# untitled.net
KiCad netlist of a schematic drawn in EAGLE
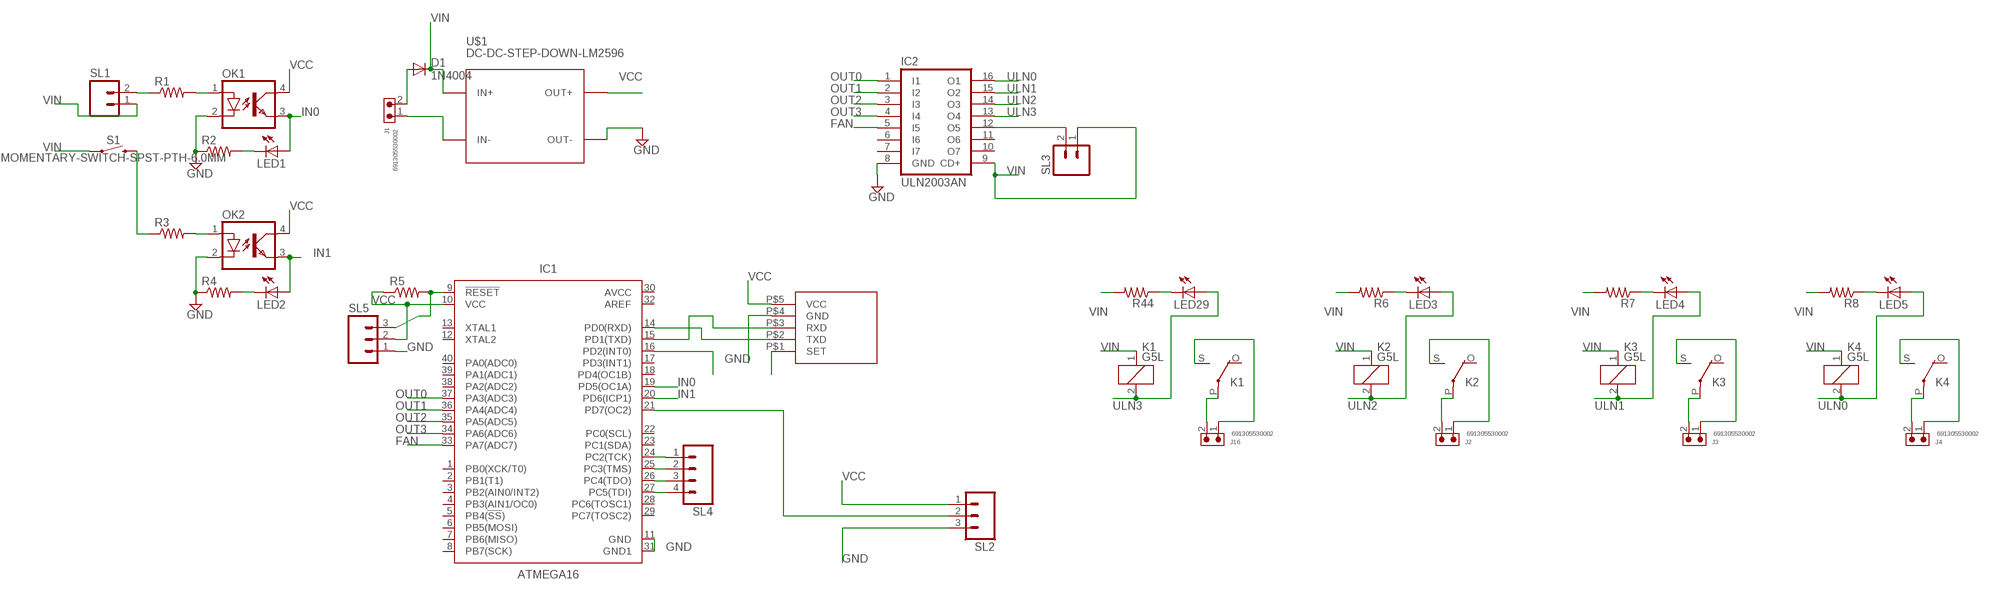
[diagram p0: schematic, sheet 1]

(export (version "E")
  (design (tool "Eeschema 10.0.6"))
  (components
    (comp (ref "D1")
      (value "1N4004")
      (footprint "eagle-import:DO41-10")
      (libsource (lib "eagle-import") (part "1N4004"))
    )
    (comp (ref "IC1")
      (value "ATMEGA16")
      (footprint "eagle-import:DIP1587W56P254L5229H482Q40B")
      (fields (field (name "MANUFACTURER") "Microchip Technology") (field (name "MPN") "ATMEGA32-16PU"))
      (libsource (lib "eagle-import") (part "ATMEGA32DIP-16PU_"))
    )
    (comp (ref "IC2")
      (value "ULN2003AN")
      (footprint "eagle-import:DIL16")
      (libsource (lib "eagle-import") (part "ULN2003AN"))
    )
    (comp (ref "J1")
      (value "691305530002")
      (footprint "eagle-import:691305530002")
      (libsource (lib "eagle-import") (part "691305530002"))
    )
    (comp (ref "J2")
      (value "691305530002")
      (footprint "eagle-import:691305530002")
      (libsource (lib "eagle-import") (part "691305530002"))
    )
    (comp (ref "J3")
      (value "691305530002")
      (footprint "eagle-import:691305530002")
      (libsource (lib "eagle-import") (part "691305530002"))
    )
    (comp (ref "J4")
      (value "691305530002")
      (footprint "eagle-import:691305530002")
      (libsource (lib "eagle-import") (part "691305530002"))
    )
    (comp (ref "J16")
      (value "691305530002")
      (footprint "eagle-import:691305530002")
      (libsource (lib "eagle-import") (part "691305530002"))
    )
    (comp (ref "K1")
      (value "G5L")
      (footprint "eagle-import:G5LE")
      (libsource (lib "eagle-import") (part "G5L"))
    )
    (comp (ref "K2")
      (value "G5L")
      (footprint "eagle-import:G5LE")
      (libsource (lib "eagle-import") (part "G5L"))
    )
    (comp (ref "K3")
      (value "G5L")
      (footprint "eagle-import:G5LE")
      (libsource (lib "eagle-import") (part "G5L"))
    )
    (comp (ref "K4")
      (value "G5L")
      (footprint "eagle-import:G5LE")
      (libsource (lib "eagle-import") (part "G5L"))
    )
    (comp (ref "LED1")
      (value "LED5MM")
      (footprint "eagle-import:LED5MM")
      (libsource (lib "eagle-import") (part "LED5MM"))
    )
    (comp (ref "LED2")
      (value "LED5MM")
      (footprint "eagle-import:LED5MM")
      (libsource (lib "eagle-import") (part "LED5MM"))
    )
    (comp (ref "LED3")
      (value "LED5MM")
      (footprint "eagle-import:LED5MM")
      (libsource (lib "eagle-import") (part "LED5MM"))
    )
    (comp (ref "LED4")
      (value "LED5MM")
      (footprint "eagle-import:LED5MM")
      (libsource (lib "eagle-import") (part "LED5MM"))
    )
    (comp (ref "LED5")
      (value "LED5MM")
      (footprint "eagle-import:LED5MM")
      (libsource (lib "eagle-import") (part "LED5MM"))
    )
    (comp (ref "LED29")
      (value "LED5MM")
      (footprint "eagle-import:LED5MM")
      (libsource (lib "eagle-import") (part "LED5MM"))
    )
    (comp (ref "OK1")
      (value "PC817")
      (footprint "eagle-import:DIL04")
      (fields (field (name "MPN") "PC817X4J000F"))
      (libsource (lib "eagle-import") (part "PC817"))
    )
    (comp (ref "OK2")
      (value "PC817")
      (footprint "eagle-import:DIL04")
      (fields (field (name "MPN") "PC817X4J000F"))
      (libsource (lib "eagle-import") (part "PC817"))
    )
    (comp (ref "R1")
      (value "R-US_0207/7")
      (footprint "eagle-import:0207_7")
      (libsource (lib "eagle-import") (part "R-US_0207/7"))
    )
    (comp (ref "R2")
      (value "R-US_0207/7")
      (footprint "eagle-import:0207_7")
      (libsource (lib "eagle-import") (part "R-US_0207/7"))
    )
    (comp (ref "R3")
      (value "R-US_0207/7")
      (footprint "eagle-import:0207_7")
      (libsource (lib "eagle-import") (part "R-US_0207/7"))
    )
    (comp (ref "R4")
      (value "R-US_0207/7")
      (footprint "eagle-import:0207_7")
      (libsource (lib "eagle-import") (part "R-US_0207/7"))
    )
    (comp (ref "R5")
      (value "R-US_0207/7")
      (footprint "eagle-import:0207_7")
      (libsource (lib "eagle-import") (part "R-US_0207/7"))
    )
    (comp (ref "R6")
      (value "R-US_0207/7")
      (footprint "eagle-import:0207_7")
      (libsource (lib "eagle-import") (part "R-US_0207/7"))
    )
    (comp (ref "R7")
      (value "R-US_0207/7")
      (footprint "eagle-import:0207_7")
      (libsource (lib "eagle-import") (part "R-US_0207/7"))
    )
    (comp (ref "R8")
      (value "R-US_0207/7")
      (footprint "eagle-import:0207_7")
      (libsource (lib "eagle-import") (part "R-US_0207/7"))
    )
    (comp (ref "R44")
      (value "R-US_0207/7")
      (footprint "eagle-import:0207_7")
      (libsource (lib "eagle-import") (part "R-US_0207/7"))
    )
    (comp (ref "S1")
      (value "MOMENTARY-SWITCH-SPST-PTH-6.0MM")
      (footprint "eagle-import:TACTILE_SWITCH_PTH_6.0MM")
      (libsource (lib "eagle-import") (part "MOMENTARY-SWITCH-SPST-PTH-6.0MM"))
    )
    (comp (ref "SL1")
      (value "M02")
      (footprint "eagle-import:02P")
      (libsource (lib "eagle-import") (part "M02"))
    )
    (comp (ref "SL2")
      (value "M03")
      (footprint "eagle-import:03P")
      (libsource (lib "eagle-import") (part "M03"))
    )
    (comp (ref "SL3")
      (value "M02")
      (footprint "eagle-import:02P")
      (libsource (lib "eagle-import") (part "M02"))
    )
    (comp (ref "SL4")
      (value "M04")
      (footprint "eagle-import:04P")
      (libsource (lib "eagle-import") (part "M04"))
    )
    (comp (ref "SL5")
      (value "M03")
      (footprint "eagle-import:03P")
      (libsource (lib "eagle-import") (part "M03"))
    )
    (comp (ref "U$1")
      (value "DC-DC-STEP-DOWN-LM2596")
      (footprint "eagle-import:DC-DC-STEP-DOWN-LM2596")
      (libsource (lib "eagle-import") (part "DC-DC-STEP-DOWN-LM2596"))
    )
    (comp (ref "U$2")
      (value "HC12")
      (footprint "eagle-import:HC12")
      (libsource (lib "eagle-import") (part "HC12"))
    )
  )
  (nets
    (net (code "1") (name "/AVCC") (class "Default")
      (node (ref "IC1") (pin "30") (pinfunction "AVCC_30") (pintype "power_in"))
    )
    (net (code "2") (name "/FAN") (class "Default")
      (node (ref "IC1") (pin "33") (pinfunction "PA7(ADC7)_33") (pintype "bidirectional"))
      (node (ref "IC2") (pin "5") (pinfunction "I5_5") (pintype "input"))
    )
    (net (code "3") (name "/IN0") (class "Default")
      (node (ref "IC1") (pin "19") (pinfunction "PD5(OC1A)_19") (pintype "bidirectional"))
      (node (ref "LED1") (pin "A") (pinfunction "A_A") (pintype "passive"))
      (node (ref "OK1") (pin "3") (pinfunction "EMIT_3") (pintype "passive"))
    )
    (net (code "4") (name "/IN1") (class "Default")
      (node (ref "IC1") (pin "20") (pinfunction "PD6(ICP1)_20") (pintype "bidirectional"))
      (node (ref "LED2") (pin "A") (pinfunction "A_A") (pintype "passive"))
      (node (ref "OK2") (pin "3") (pinfunction "EMIT_3") (pintype "passive"))
    )
    (net (code "5") (name "/OUT0") (class "Default")
      (node (ref "IC1") (pin "37") (pinfunction "PA3(ADC3)_37") (pintype "bidirectional"))
      (node (ref "IC2") (pin "1") (pinfunction "I1_1") (pintype "input"))
    )
    (net (code "6") (name "/OUT1") (class "Default")
      (node (ref "IC1") (pin "36") (pinfunction "PA4(ADC4)_36") (pintype "bidirectional"))
      (node (ref "IC2") (pin "2") (pinfunction "I2_2") (pintype "input"))
    )
    (net (code "7") (name "/OUT2") (class "Default")
      (node (ref "IC1") (pin "35") (pinfunction "PA5(ADC5)_35") (pintype "bidirectional"))
      (node (ref "IC2") (pin "3") (pinfunction "I3_3") (pintype "input"))
    )
    (net (code "8") (name "/OUT3") (class "Default")
      (node (ref "IC1") (pin "34") (pinfunction "PA6(ADC6)_34") (pintype "bidirectional"))
      (node (ref "IC2") (pin "4") (pinfunction "I4_4") (pintype "input"))
    )
    (net (code "9") (name "/ULN0") (class "Default")
      (node (ref "IC2") (pin "16") (pinfunction "O1_16") (pintype "open_collector"))
      (node (ref "K4") (pin "2") (pinfunction "2_2") (pintype "passive"))
      (node (ref "LED5") (pin "A") (pinfunction "A_A") (pintype "passive"))
    )
    (net (code "10") (name "/ULN1") (class "Default")
      (node (ref "IC2") (pin "15") (pinfunction "O2_15") (pintype "open_collector"))
      (node (ref "K3") (pin "2") (pinfunction "2_2") (pintype "passive"))
      (node (ref "LED4") (pin "A") (pinfunction "A_A") (pintype "passive"))
    )
    (net (code "11") (name "/ULN2") (class "Default")
      (node (ref "IC2") (pin "14") (pinfunction "O3_14") (pintype "open_collector"))
      (node (ref "K2") (pin "2") (pinfunction "2_2") (pintype "passive"))
      (node (ref "LED3") (pin "A") (pinfunction "A_A") (pintype "passive"))
    )
    (net (code "12") (name "/ULN3") (class "Default")
      (node (ref "IC2") (pin "13") (pinfunction "O4_13") (pintype "open_collector"))
      (node (ref "K1") (pin "2") (pinfunction "2_2") (pintype "passive"))
      (node (ref "LED29") (pin "A") (pinfunction "A_A") (pintype "passive"))
    )
    (net (code "13") (name "/VCC") (class "Default")
      (node (ref "IC1") (pin "10") (pinfunction "VCC_10") (pintype "power_in"))
      (node (ref "OK1") (pin "4") (pinfunction "COL_4") (pintype "passive"))
      (node (ref "OK2") (pin "4") (pinfunction "COL_4") (pintype "passive"))
      (node (ref "R5") (pin "1") (pinfunction "1_1") (pintype "passive"))
      (node (ref "SL2") (pin "1") (pinfunction "1_1") (pintype "passive"))
      (node (ref "SL5") (pin "2") (pinfunction "2_2") (pintype "passive"))
      (node (ref "U$1") (pin "OUT+") (pinfunction "OUT+_OUT+") (pintype "bidirectional"))
      (node (ref "U$2") (pin "P$5") (pinfunction "VCC_P$5") (pintype "bidirectional"))
    )
    (net (code "14") (name "/VIN") (class "Default")
      (node (ref "D1") (pin "C") (pinfunction "C_C") (pintype "passive"))
      (node (ref "IC2") (pin "9") (pinfunction "CD+_9") (pintype "passive"))
      (node (ref "K1") (pin "1") (pinfunction "1_1") (pintype "passive"))
      (node (ref "K2") (pin "1") (pinfunction "1_1") (pintype "passive"))
      (node (ref "K3") (pin "1") (pinfunction "1_1") (pintype "passive"))
      (node (ref "K4") (pin "1") (pinfunction "1_1") (pintype "passive"))
      (node (ref "R44") (pin "2") (pinfunction "2_2") (pintype "passive"))
      (node (ref "R6") (pin "2") (pinfunction "2_2") (pintype "passive"))
      (node (ref "R7") (pin "2") (pinfunction "2_2") (pintype "passive"))
      (node (ref "R8") (pin "2") (pinfunction "2_2") (pintype "passive"))
      (node (ref "S1") (pin "1") (pinfunction "1_1") (pintype "passive"))
      (node (ref "SL1") (pin "1") (pinfunction "1_1") (pintype "passive"))
      (node (ref "SL3") (pin "1") (pinfunction "1_1") (pintype "passive"))
      (node (ref "U$1") (pin "IN+") (pinfunction "IN+_IN+") (pintype "bidirectional"))
    )
    (net (code "15") (name "GND") (class "Default")
      (node (ref "IC1") (pin "11") (pinfunction "GND_11") (pintype "power_in"))
      (node (ref "IC1") (pin "31") (pinfunction "GND1_31") (pintype "power_in"))
      (node (ref "IC2") (pin "8") (pinfunction "GND_8") (pintype "power_in"))
      (node (ref "OK1") (pin "2") (pinfunction "C_2") (pintype "passive"))
      (node (ref "OK2") (pin "2") (pinfunction "C_2") (pintype "passive"))
      (node (ref "R2") (pin "1") (pinfunction "1_1") (pintype "passive"))
      (node (ref "R4") (pin "1") (pinfunction "1_1") (pintype "passive"))
      (node (ref "SL2") (pin "3") (pinfunction "3_3") (pintype "passive"))
      (node (ref "SL5") (pin "1") (pinfunction "1_1") (pintype "passive"))
      (node (ref "U$1") (pin "OUT-") (pinfunction "OUT-_OUT-") (pintype "bidirectional"))
      (node (ref "U$2") (pin "P$4") (pinfunction "GND_P$4") (pintype "bidirectional"))
    )
    (net (code "16") (name "Net-(D1-PadA)") (class "Default")
      (node (ref "D1") (pin "A") (pinfunction "A_A") (pintype "passive"))
      (node (ref "J1") (pin "2") (pinfunction "2_2") (pintype "passive"))
    )
    (net (code "17") (name "Net-(IC1-PC2(TCK))") (class "Default")
      (node (ref "IC1") (pin "24") (pinfunction "PC2(TCK)_24") (pintype "input"))
      (node (ref "SL4") (pin "1") (pinfunction "1_1") (pintype "passive"))
    )
    (net (code "18") (name "Net-(IC1-PC3(TMS))") (class "Default")
      (node (ref "IC1") (pin "25") (pinfunction "PC3(TMS)_25") (pintype "input"))
      (node (ref "SL4") (pin "2") (pinfunction "2_2") (pintype "passive"))
    )
    (net (code "19") (name "Net-(IC1-PC4(TDO))") (class "Default")
      (node (ref "IC1") (pin "26") (pinfunction "PC4(TDO)_26") (pintype "output"))
      (node (ref "SL4") (pin "3") (pinfunction "3_3") (pintype "passive"))
    )
    (net (code "20") (name "Net-(IC1-PC5(TDI))") (class "Default")
      (node (ref "IC1") (pin "27") (pinfunction "PC5(TDI)_27") (pintype "input"))
      (node (ref "SL4") (pin "4") (pinfunction "4_4") (pintype "passive"))
    )
    (net (code "21") (name "Net-(IC1-PD0(RXD))") (class "Default")
      (node (ref "IC1") (pin "14") (pinfunction "PD0(RXD)_14") (pintype "bidirectional"))
      (node (ref "U$2") (pin "P$2") (pinfunction "TXD_P$2") (pintype "bidirectional"))
    )
    (net (code "22") (name "Net-(IC1-PD1(TXD))") (class "Default")
      (node (ref "IC1") (pin "15") (pinfunction "PD1(TXD)_15") (pintype "bidirectional"))
      (node (ref "U$2") (pin "P$3") (pinfunction "RXD_P$3") (pintype "bidirectional"))
    )
    (net (code "23") (name "Net-(IC1-PD7(OC2))") (class "Default")
      (node (ref "IC1") (pin "21") (pinfunction "PD7(OC2)_21") (pintype "bidirectional"))
      (node (ref "SL2") (pin "2") (pinfunction "2_2") (pintype "passive"))
    )
    (net (code "24") (name "Net-(IC1-~{RESET})") (class "Default")
      (node (ref "IC1") (pin "9") (pinfunction "~{RESET}_9") (pintype "input"))
      (node (ref "R5") (pin "2") (pinfunction "2_2") (pintype "passive"))
      (node (ref "SL5") (pin "3") (pinfunction "3_3") (pintype "passive"))
    )
    (net (code "25") (name "Net-(IC2-O5)") (class "Default")
      (node (ref "IC2") (pin "12") (pinfunction "O5_12") (pintype "open_collector"))
      (node (ref "SL3") (pin "2") (pinfunction "2_2") (pintype "passive"))
    )
    (net (code "26") (name "Net-(J1-Pad1)") (class "Default")
      (node (ref "J1") (pin "1") (pinfunction "1_1") (pintype "passive"))
      (node (ref "U$1") (pin "IN-") (pinfunction "IN-_IN-") (pintype "bidirectional"))
    )
    (net (code "27") (name "Net-(J2-Pad1)") (class "Default")
      (node (ref "J2") (pin "1") (pinfunction "1_1") (pintype "passive"))
      (node (ref "K2") (pin "S") (pinfunction "S_S") (pintype "passive"))
    )
    (net (code "28") (name "Net-(J2-Pad2)") (class "Default")
      (node (ref "J2") (pin "2") (pinfunction "2_2") (pintype "passive"))
      (node (ref "K2") (pin "P") (pinfunction "P_P") (pintype "passive"))
    )
    (net (code "29") (name "Net-(J3-Pad1)") (class "Default")
      (node (ref "J3") (pin "1") (pinfunction "1_1") (pintype "passive"))
      (node (ref "K3") (pin "S") (pinfunction "S_S") (pintype "passive"))
    )
    (net (code "30") (name "Net-(J3-Pad2)") (class "Default")
      (node (ref "J3") (pin "2") (pinfunction "2_2") (pintype "passive"))
      (node (ref "K3") (pin "P") (pinfunction "P_P") (pintype "passive"))
    )
    (net (code "31") (name "Net-(J4-Pad1)") (class "Default")
      (node (ref "J4") (pin "1") (pinfunction "1_1") (pintype "passive"))
      (node (ref "K4") (pin "S") (pinfunction "S_S") (pintype "passive"))
    )
    (net (code "32") (name "Net-(J4-Pad2)") (class "Default")
      (node (ref "J4") (pin "2") (pinfunction "2_2") (pintype "passive"))
      (node (ref "K4") (pin "P") (pinfunction "P_P") (pintype "passive"))
    )
    (net (code "33") (name "Net-(J16-Pad1)") (class "Default")
      (node (ref "J16") (pin "1") (pinfunction "1_1") (pintype "passive"))
      (node (ref "K1") (pin "S") (pinfunction "S_S") (pintype "passive"))
    )
    (net (code "34") (name "Net-(J16-Pad2)") (class "Default")
      (node (ref "J16") (pin "2") (pinfunction "2_2") (pintype "passive"))
      (node (ref "K1") (pin "P") (pinfunction "P_P") (pintype "passive"))
    )
    (net (code "35") (name "Net-(LED1-C)") (class "Default")
      (node (ref "LED1") (pin "K") (pinfunction "C_K") (pintype "passive"))
      (node (ref "R2") (pin "2") (pinfunction "2_2") (pintype "passive"))
    )
    (net (code "36") (name "Net-(LED2-C)") (class "Default")
      (node (ref "LED2") (pin "K") (pinfunction "C_K") (pintype "passive"))
      (node (ref "R4") (pin "2") (pinfunction "2_2") (pintype "passive"))
    )
    (net (code "37") (name "Net-(LED3-C)") (class "Default")
      (node (ref "LED3") (pin "K") (pinfunction "C_K") (pintype "passive"))
      (node (ref "R6") (pin "1") (pinfunction "1_1") (pintype "passive"))
    )
    (net (code "38") (name "Net-(LED4-C)") (class "Default")
      (node (ref "LED4") (pin "K") (pinfunction "C_K") (pintype "passive"))
      (node (ref "R7") (pin "1") (pinfunction "1_1") (pintype "passive"))
    )
    (net (code "39") (name "Net-(LED5-C)") (class "Default")
      (node (ref "LED5") (pin "K") (pinfunction "C_K") (pintype "passive"))
      (node (ref "R8") (pin "1") (pinfunction "1_1") (pintype "passive"))
    )
    (net (code "40") (name "Net-(LED29-C)") (class "Default")
      (node (ref "LED29") (pin "K") (pinfunction "C_K") (pintype "passive"))
      (node (ref "R44") (pin "1") (pinfunction "1_1") (pintype "passive"))
    )
    (net (code "41") (name "Net-(OK1-A)") (class "Default")
      (node (ref "OK1") (pin "1") (pinfunction "A_1") (pintype "passive"))
      (node (ref "R1") (pin "2") (pinfunction "2_2") (pintype "passive"))
    )
    (net (code "42") (name "Net-(OK2-A)") (class "Default")
      (node (ref "OK2") (pin "1") (pinfunction "A_1") (pintype "passive"))
      (node (ref "R3") (pin "2") (pinfunction "2_2") (pintype "passive"))
    )
    (net (code "43") (name "Net-(R1-Pad1)") (class "Default")
      (node (ref "R1") (pin "1") (pinfunction "1_1") (pintype "passive"))
      (node (ref "SL1") (pin "2") (pinfunction "2_2") (pintype "passive"))
    )
    (net (code "44") (name "Net-(S1-2)") (class "Default")
      (node (ref "R3") (pin "1") (pinfunction "1_1") (pintype "passive"))
      (node (ref "S1") (pin "3") (pinfunction "2_3") (pintype "passive"))
    )
    (net (code "45") (name "unconnected-(IC1-AREF-Pad32)") (class "Default")
      (node (ref "IC1") (pin "32") (pinfunction "AREF_32") (pintype "passive"))
    )
    (net (code "46") (name "unconnected-(IC1-PA0(ADC0)-Pad40)") (class "Default")
      (node (ref "IC1") (pin "40") (pinfunction "PA0(ADC0)_40") (pintype "bidirectional"))
    )
    (net (code "47") (name "unconnected-(IC1-PA1(ADC1)-Pad39)") (class "Default")
      (node (ref "IC1") (pin "39") (pinfunction "PA1(ADC1)_39") (pintype "bidirectional"))
    )
    (net (code "48") (name "unconnected-(IC1-PA2(ADC2)-Pad38)") (class "Default")
      (node (ref "IC1") (pin "38") (pinfunction "PA2(ADC2)_38") (pintype "bidirectional"))
    )
    (net (code "49") (name "unconnected-(IC1-PB0(XCK{slash}T0)-Pad1)") (class "Default")
      (node (ref "IC1") (pin "1") (pinfunction "PB0(XCK/T0)_1") (pintype "bidirectional"))
    )
    (net (code "50") (name "unconnected-(IC1-PB1(T1)-Pad2)") (class "Default")
      (node (ref "IC1") (pin "2") (pinfunction "PB1(T1)_2") (pintype "bidirectional"))
    )
    (net (code "51") (name "unconnected-(IC1-PB2(AIN0{slash}INT2)-Pad3)") (class "Default")
      (node (ref "IC1") (pin "3") (pinfunction "PB2(AIN0/INT2)_3") (pintype "bidirectional"))
    )
    (net (code "52") (name "unconnected-(IC1-PB3(AIN1{slash}OC0)-Pad4)") (class "Default")
      (node (ref "IC1") (pin "4") (pinfunction "PB3(AIN1/OC0)_4") (pintype "bidirectional"))
    )
    (net (code "53") (name "unconnected-(IC1-PB4(~{SS})-Pad5)") (class "Default")
      (node (ref "IC1") (pin "5") (pinfunction "PB4(~{SS})_5") (pintype "bidirectional"))
    )
    (net (code "54") (name "unconnected-(IC1-PB5(MOSI)-Pad6)") (class "Default")
      (node (ref "IC1") (pin "6") (pinfunction "PB5(MOSI)_6") (pintype "bidirectional"))
    )
    (net (code "55") (name "unconnected-(IC1-PB6(MISO)-Pad7)") (class "Default")
      (node (ref "IC1") (pin "7") (pinfunction "PB6(MISO)_7") (pintype "bidirectional"))
    )
    (net (code "56") (name "unconnected-(IC1-PB7(SCK)-Pad8)") (class "Default")
      (node (ref "IC1") (pin "8") (pinfunction "PB7(SCK)_8") (pintype "bidirectional"))
    )
    (net (code "57") (name "unconnected-(IC1-PC0(SCL)-Pad22)") (class "Default")
      (node (ref "IC1") (pin "22") (pinfunction "PC0(SCL)_22") (pintype "bidirectional"))
    )
    (net (code "58") (name "unconnected-(IC1-PC1(SDA)-Pad23)") (class "Default")
      (node (ref "IC1") (pin "23") (pinfunction "PC1(SDA)_23") (pintype "bidirectional"))
    )
    (net (code "59") (name "unconnected-(IC1-PC6(TOSC1)-Pad28)") (class "Default")
      (node (ref "IC1") (pin "28") (pinfunction "PC6(TOSC1)_28") (pintype "bidirectional"))
    )
    (net (code "60") (name "unconnected-(IC1-PC7(TOSC2)-Pad29)") (class "Default")
      (node (ref "IC1") (pin "29") (pinfunction "PC7(TOSC2)_29") (pintype "bidirectional"))
    )
    (net (code "61") (name "unconnected-(IC1-PD2(INT0)-Pad16)") (class "Default")
      (node (ref "IC1") (pin "16") (pinfunction "PD2(INT0)_16") (pintype "bidirectional"))
    )
    (net (code "62") (name "unconnected-(IC1-PD3(INT1)-Pad17)") (class "Default")
      (node (ref "IC1") (pin "17") (pinfunction "PD3(INT1)_17") (pintype "bidirectional"))
    )
    (net (code "63") (name "unconnected-(IC1-PD4(OC1B)-Pad18)") (class "Default")
      (node (ref "IC1") (pin "18") (pinfunction "PD4(OC1B)_18") (pintype "bidirectional"))
    )
    (net (code "64") (name "unconnected-(IC1-XTAL1-Pad13)") (class "Default")
      (node (ref "IC1") (pin "13") (pinfunction "XTAL1_13") (pintype "passive"))
    )
    (net (code "65") (name "unconnected-(IC1-XTAL2-Pad12)") (class "Default")
      (node (ref "IC1") (pin "12") (pinfunction "XTAL2_12") (pintype "passive"))
    )
    (net (code "66") (name "unconnected-(IC2-I6-Pad6)") (class "Default")
      (node (ref "IC2") (pin "6") (pinfunction "I6_6") (pintype "input"))
    )
    (net (code "67") (name "unconnected-(IC2-I7-Pad7)") (class "Default")
      (node (ref "IC2") (pin "7") (pinfunction "I7_7") (pintype "input"))
    )
    (net (code "68") (name "unconnected-(IC2-O6-Pad11)") (class "Default")
      (node (ref "IC2") (pin "11") (pinfunction "O6_11") (pintype "open_collector"))
    )
    (net (code "69") (name "unconnected-(IC2-O7-Pad10)") (class "Default")
      (node (ref "IC2") (pin "10") (pinfunction "O7_10") (pintype "open_collector"))
    )
    (net (code "70") (name "unconnected-(K1-PadO)") (class "Default")
      (node (ref "K1") (pin "O") (pinfunction "O_O") (pintype "passive"))
    )
    (net (code "71") (name "unconnected-(K2-PadO)") (class "Default")
      (node (ref "K2") (pin "O") (pinfunction "O_O") (pintype "passive"))
    )
    (net (code "72") (name "unconnected-(K3-PadO)") (class "Default")
      (node (ref "K3") (pin "O") (pinfunction "O_O") (pintype "passive"))
    )
    (net (code "73") (name "unconnected-(K4-PadO)") (class "Default")
      (node (ref "K4") (pin "O") (pinfunction "O_O") (pintype "passive"))
    )
    (net (code "74") (name "unconnected-(U$2-SET-PadP$1)") (class "Default")
      (node (ref "U$2") (pin "P$1") (pinfunction "SET_P$1") (pintype "bidirectional"))
    )
  )
)
